# Stepper_Driver.net
KiCad netlist of a schematic drawn in Altium Designer
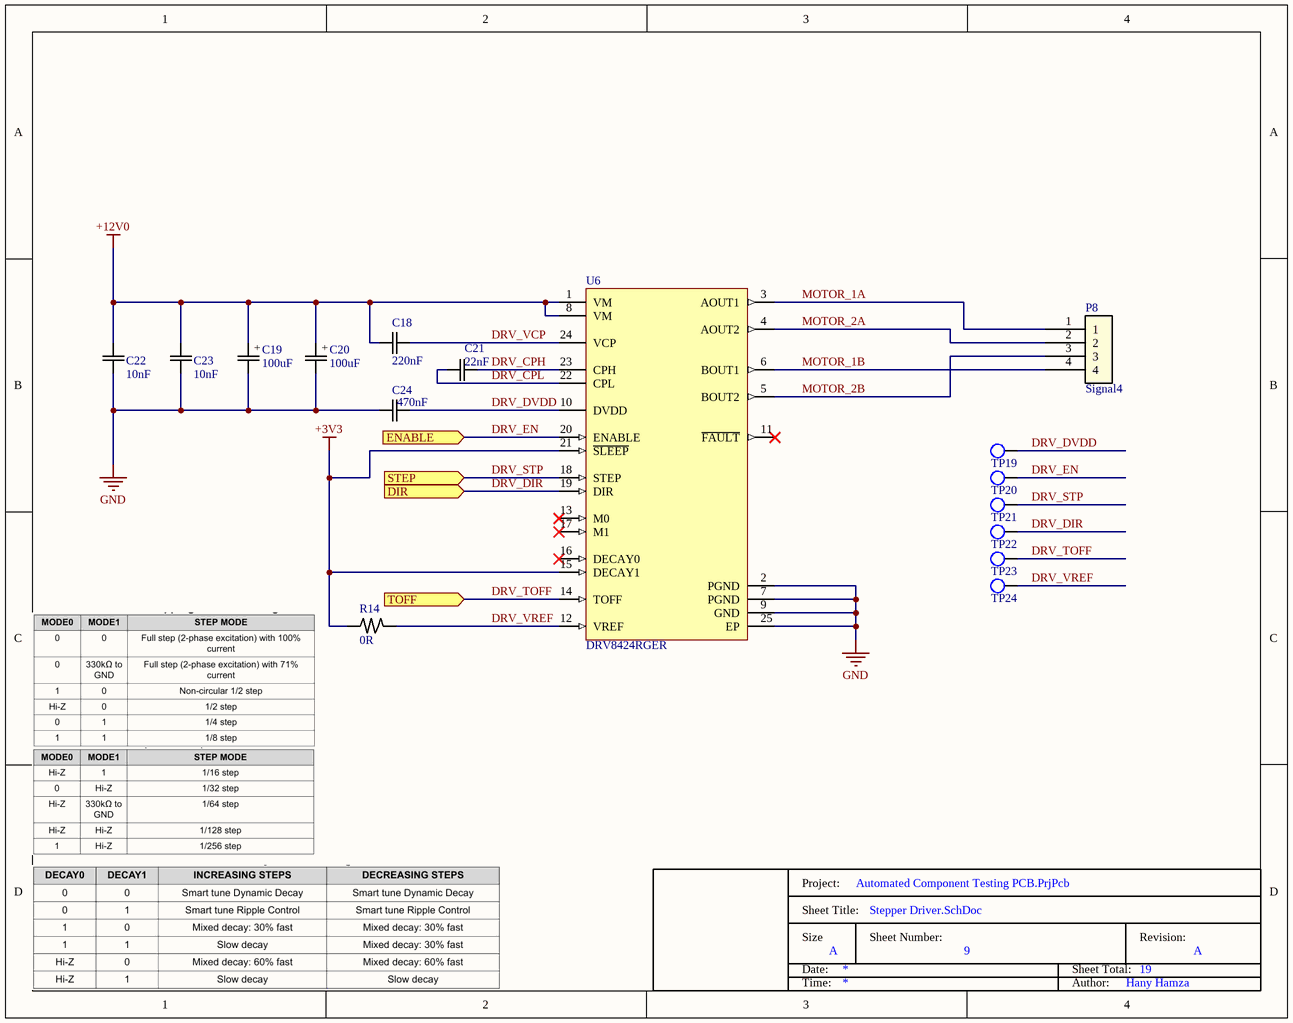
[diagram p0: Stepper Driver.SchDoc]

(export (version "E")
  (design (tool "Eeschema 10.0.6"))
  (components
    (comp (ref "C18")
      (value "220nF")
      (footprint "C0603")
      (description "CAP CER 220nF 50V X7R 0603")
      (fields (field (name "MF") "HRE") (field (name "MP") "CGA0603X7R224K500JT"))
      (libsource (lib "Components") (part "Cap_cer"))
    )
    (comp (ref "C19")
      (value "100uF")
      (footprint "CAP THT D6.3mm")
      (description "CAP ALUM 100uF ±20% 16V TH")
      (fields (field (name "MF") "Lelon") (field (name "MP") "SSG101M1CBK-0605"))
      (libsource (lib "Components") (part "Cap_alu"))
    )
    (comp (ref "C20")
      (value "100uF")
      (footprint "CAP THT D6.3mm")
      (description "CAP ALUM 100uF ±20% 16V TH")
      (fields (field (name "MF") "Lelon") (field (name "MP") "SSG101M1CBK-0605"))
      (libsource (lib "Components") (part "Cap_alu"))
    )
    (comp (ref "C21")
      (value "22nF")
      (footprint "C0603")
      (description "CAP CER 22nF 50V X7R 0603")
      (fields (field (name "MF") "CCTC") (field (name "MP") "TCC0603X7R223M500CT"))
      (libsource (lib "Components") (part "Cap_cer"))
    )
    (comp (ref "C22")
      (value "10nF")
      (footprint "C0603")
      (description "CAP CER 10nF 50V X7R 0603")
      (fields (field (name "MF") "HRE") (field (name "MP") "CGA0603X7R103M500JT"))
      (libsource (lib "Components") (part "Cap_cer"))
    )
    (comp (ref "C23")
      (value "10nF")
      (footprint "C0603")
      (description "CAP CER 10nF 50V X7R 0603")
      (fields (field (name "MF") "HRE") (field (name "MP") "CGA0603X7R103M500JT"))
      (libsource (lib "Components") (part "Cap_cer"))
    )
    (comp (ref "C24")
      (value "470nF")
      (footprint "C0603")
      (description "CAP CER 470nF 50V X7R 0603")
      (fields (field (name "MF") "Chinocera") (field (name "MP") "HGC0603R7474K500NTHJ"))
      (libsource (lib "Components") (part "Cap_cer"))
    )
    (comp (ref "P8")
      (value "Signal4")
      (footprint "Signal4")
      (description "SignalConnector, 4 leads")
      (fields (field (name "MF") "Molex") (field (name "MP") "0022232041"))
      (libsource (lib "Connectors") (part "Signal4"))
    )
    (comp (ref "R14")
      (value "0R")
      (footprint "R0603")
      (description "RES 0Ω ±5% 100mW 0603")
      (fields (field (name "MF") "VO") (field (name "MP") "SCR0603J0R"))
      (libsource (lib "Components") (part "Res"))
    )
    (comp (ref "TP19")
      (value "TestPoint")
      (footprint "TESTPOINT_SMD_1.27MM")
      (libsource (lib "Components") (part "TestPoint"))
    )
    (comp (ref "TP20")
      (value "TestPoint")
      (footprint "TESTPOINT_SMD_1.27MM")
      (libsource (lib "Components") (part "TestPoint"))
    )
    (comp (ref "TP21")
      (value "TestPoint")
      (footprint "TESTPOINT_SMD_1.27MM")
      (libsource (lib "Components") (part "TestPoint"))
    )
    (comp (ref "TP22")
      (value "TestPoint")
      (footprint "TESTPOINT_SMD_1.27MM")
      (libsource (lib "Components") (part "TestPoint"))
    )
    (comp (ref "TP23")
      (value "TestPoint")
      (footprint "TESTPOINT_SMD_1.27MM")
      (libsource (lib "Components") (part "TestPoint"))
    )
    (comp (ref "TP24")
      (value "TestPoint")
      (footprint "TESTPOINT_SMD_1.27MM")
      (libsource (lib "Components") (part "TestPoint"))
    )
    (comp (ref "U6")
      (value "DRV8424RGER")
      (footprint "DRV8425RGER")
      (fields (field (name "MF") "Texas Instruments"))
      (libsource (lib "Components") (part "DRV8424RGER"))
    )
  )
  (nets
    (net (code "1") (name "+3V3") (class "Default")
      (node (ref "R14") (pin "1") (pinfunction "1_1") (pintype "passive"))
      (node (ref "U6") (pin "15") (pinfunction "DECAY1_15") (pintype "input"))
      (node (ref "U6") (pin "21") (pinfunction "~{SLEEP}_21") (pintype "input"))
    )
    (net (code "2") (name "+12V0") (class "Default")
      (node (ref "C18") (pin "1") (pinfunction "1_1") (pintype "passive"))
      (node (ref "C19") (pin "1") (pinfunction "+_1") (pintype "passive"))
      (node (ref "C20") (pin "1") (pinfunction "+_1") (pintype "passive"))
      (node (ref "C22") (pin "1") (pinfunction "1_1") (pintype "passive"))
      (node (ref "C23") (pin "1") (pinfunction "1_1") (pintype "passive"))
      (node (ref "U6") (pin "1") (pinfunction "VM_1") (pintype "power_in"))
      (node (ref "U6") (pin "8") (pinfunction "VM_8") (pintype "power_in"))
    )
    (net (code "3") (name "/DRV_CPH") (class "Default")
      (node (ref "C21") (pin "2") (pinfunction "2_2") (pintype "passive"))
      (node (ref "U6") (pin "23") (pinfunction "CPH_23") (pintype "passive"))
    )
    (net (code "4") (name "/DRV_CPL") (class "Default")
      (node (ref "C21") (pin "1") (pinfunction "1_1") (pintype "passive"))
      (node (ref "U6") (pin "22") (pinfunction "CPL_22") (pintype "passive"))
    )
    (net (code "5") (name "/DRV_DIR") (class "Default")
      (node (ref "TP22") (pin "1") (pinfunction "1_1") (pintype "passive"))
      (node (ref "U6") (pin "19") (pinfunction "DIR_19") (pintype "input"))
    )
    (net (code "6") (name "/DRV_DVDD") (class "Default")
      (node (ref "C24") (pin "2") (pinfunction "2_2") (pintype "passive"))
      (node (ref "TP19") (pin "1") (pinfunction "1_1") (pintype "passive"))
      (node (ref "U6") (pin "10") (pinfunction "DVDD_10") (pintype "power_in"))
    )
    (net (code "7") (name "/DRV_EN") (class "Default")
      (node (ref "TP20") (pin "1") (pinfunction "1_1") (pintype "passive"))
      (node (ref "U6") (pin "20") (pinfunction "ENABLE_20") (pintype "input"))
    )
    (net (code "8") (name "/DRV_STP") (class "Default")
      (node (ref "TP21") (pin "1") (pinfunction "1_1") (pintype "passive"))
      (node (ref "U6") (pin "18") (pinfunction "STEP_18") (pintype "input"))
    )
    (net (code "9") (name "/DRV_TOFF") (class "Default")
      (node (ref "TP23") (pin "1") (pinfunction "1_1") (pintype "passive"))
      (node (ref "U6") (pin "14") (pinfunction "TOFF_14") (pintype "input"))
    )
    (net (code "10") (name "/DRV_VCP") (class "Default")
      (node (ref "C18") (pin "2") (pinfunction "2_2") (pintype "passive"))
      (node (ref "U6") (pin "24") (pinfunction "VCP_24") (pintype "passive"))
    )
    (net (code "11") (name "/DRV_VREF") (class "Default")
      (node (ref "R14") (pin "2") (pinfunction "2_2") (pintype "passive"))
      (node (ref "TP24") (pin "1") (pinfunction "1_1") (pintype "passive"))
      (node (ref "U6") (pin "12") (pinfunction "VREF_12") (pintype "input"))
    )
    (net (code "12") (name "/MOTOR_1A") (class "Default")
      (node (ref "P8") (pin "1") (pinfunction "1_1") (pintype "passive"))
      (node (ref "U6") (pin "3") (pinfunction "AOUT1_3") (pintype "output"))
    )
    (net (code "13") (name "/MOTOR_1B") (class "Default")
      (node (ref "P8") (pin "4") (pinfunction "4_4") (pintype "passive"))
      (node (ref "U6") (pin "6") (pinfunction "BOUT1_6") (pintype "output"))
    )
    (net (code "14") (name "/MOTOR_2A") (class "Default")
      (node (ref "P8") (pin "2") (pinfunction "2_2") (pintype "passive"))
      (node (ref "U6") (pin "4") (pinfunction "AOUT2_4") (pintype "output"))
    )
    (net (code "15") (name "/MOTOR_2B") (class "Default")
      (node (ref "P8") (pin "3") (pinfunction "3_3") (pintype "passive"))
      (node (ref "U6") (pin "5") (pinfunction "BOUT2_5") (pintype "output"))
    )
    (net (code "16") (name "GND") (class "Default")
      (node (ref "C19") (pin "2") (pinfunction "-_2") (pintype "passive"))
      (node (ref "C20") (pin "2") (pinfunction "-_2") (pintype "passive"))
      (node (ref "C22") (pin "2") (pinfunction "2_2") (pintype "passive"))
      (node (ref "C23") (pin "2") (pinfunction "2_2") (pintype "passive"))
      (node (ref "C24") (pin "1") (pinfunction "1_1") (pintype "passive"))
      (node (ref "U6") (pin "2") (pinfunction "PGND_2") (pintype "power_in"))
      (node (ref "U6") (pin "25") (pinfunction "EP_25") (pintype "passive"))
      (node (ref "U6") (pin "7") (pinfunction "PGND_7") (pintype "power_in"))
      (node (ref "U6") (pin "9") (pinfunction "GND_9") (pintype "power_in"))
    )
    (net (code "17") (name "unconnected-(U6-DECAY0-Pad16)") (class "Default")
      (node (ref "U6") (pin "16") (pinfunction "DECAY0_16") (pintype "input+no_connect"))
    )
    (net (code "18") (name "unconnected-(U6-M0-Pad13)") (class "Default")
      (node (ref "U6") (pin "13") (pinfunction "M0_13") (pintype "input+no_connect"))
    )
    (net (code "19") (name "unconnected-(U6-M1-Pad17)") (class "Default")
      (node (ref "U6") (pin "17") (pinfunction "M1_17") (pintype "input+no_connect"))
    )
    (net (code "20") (name "unconnected-(U6-~{FAULT}-Pad11)") (class "Default")
      (node (ref "U6") (pin "11") (pinfunction "~{FAULT}_11") (pintype "output+no_connect"))
    )
  )
)
